# Micro_Control_Board_-_V130.net
KiCad netlist of a schematic drawn in EAGLE
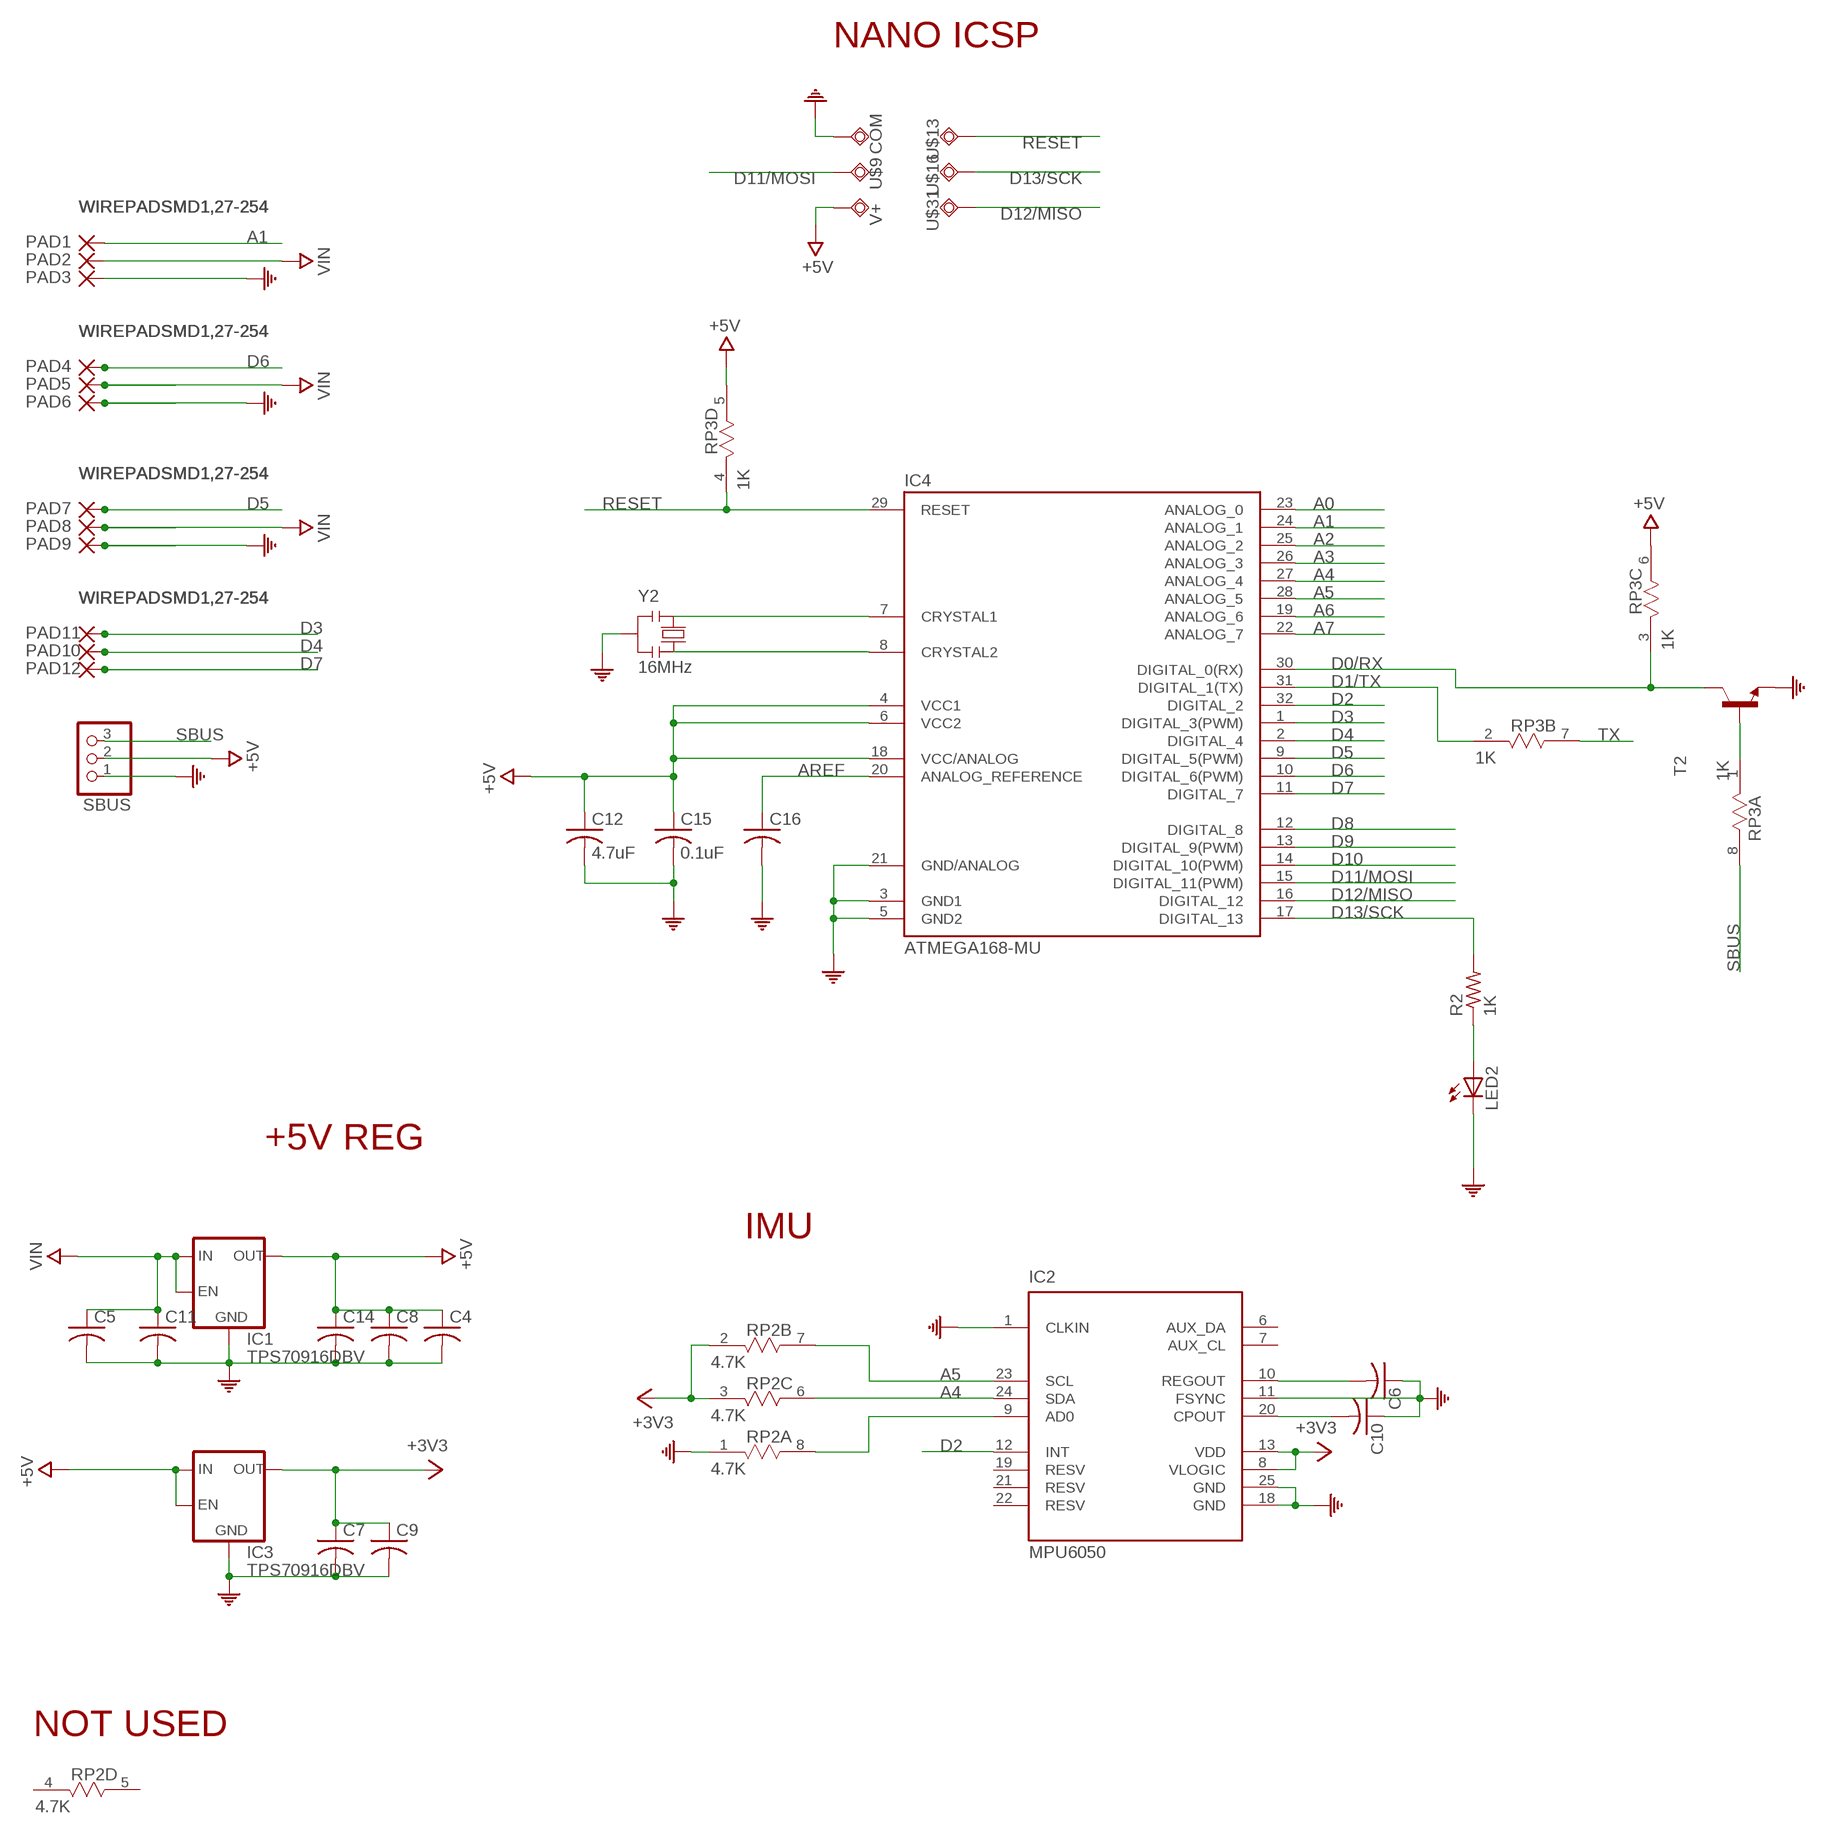
[diagram p0: schematic, sheet 1]

(export (version "E")
  (design (tool "Eeschema 10.0.6"))
  (components
    (comp (ref "C4")
      (value "C-USC0402")
      (footprint "eagle-import:C0402")
      (libsource (lib "eagle-import") (part "C-USC0402"))
    )
    (comp (ref "C5")
      (value "C-USC0402")
      (footprint "eagle-import:C0402")
      (libsource (lib "eagle-import") (part "C-USC0402"))
    )
    (comp (ref "C6")
      (value "C-USC0402")
      (footprint "eagle-import:C0402")
      (libsource (lib "eagle-import") (part "C-USC0402"))
    )
    (comp (ref "C7")
      (value "C-USC0402")
      (footprint "eagle-import:C0402")
      (libsource (lib "eagle-import") (part "C-USC0402"))
    )
    (comp (ref "C8")
      (value "C-USC0402")
      (footprint "eagle-import:C0402")
      (libsource (lib "eagle-import") (part "C-USC0402"))
    )
    (comp (ref "C9")
      (value "C-USC0402")
      (footprint "eagle-import:C0402")
      (libsource (lib "eagle-import") (part "C-USC0402"))
    )
    (comp (ref "C10")
      (value "C-USC0402")
      (footprint "eagle-import:C0402")
      (libsource (lib "eagle-import") (part "C-USC0402"))
    )
    (comp (ref "C11")
      (value "C-USC0402")
      (footprint "eagle-import:C0402")
      (libsource (lib "eagle-import") (part "C-USC0402"))
    )
    (comp (ref "C12")
      (value "4.7uF")
      (footprint "eagle-import:C0402")
      (libsource (lib "eagle-import") (part "C-USC0402"))
    )
    (comp (ref "C14")
      (value "C-USC0402")
      (footprint "eagle-import:C0402")
      (libsource (lib "eagle-import") (part "C-USC0402"))
    )
    (comp (ref "C15")
      (value "0.1uF")
      (footprint "eagle-import:C0402")
      (libsource (lib "eagle-import") (part "C-USC0402"))
    )
    (comp (ref "C16")
      (value "C-USC0402")
      (footprint "eagle-import:C0402")
      (libsource (lib "eagle-import") (part "C-USC0402"))
    )
    (comp (ref "COM")
      (value "0.7MM-THRU")
      (footprint "eagle-import:0.65MM-THRU")
      (libsource (lib "eagle-import") (part "0.7MM-THRU"))
    )
    (comp (ref "IC1")
      (value "TPS70916DBV")
      (footprint "eagle-import:SOT23-5")
      (fields (field (name "MF") "Texas Instruments") (field (name "MPN") "TPS70916DBVT"))
      (libsource (lib "eagle-import") (part "TPS709DBV16"))
    )
    (comp (ref "IC2")
      (value "MPU6050")
      (footprint "eagle-import:QFN50P400X400X95-25T265X275N")
      (libsource (lib "eagle-import") (part "MPU6050"))
    )
    (comp (ref "IC3")
      (value "TPS70916DBV")
      (footprint "eagle-import:SOT23-5")
      (fields (field (name "MF") "Texas Instruments") (field (name "MPN") "TPS70916DBVT"))
      (libsource (lib "eagle-import") (part "TPS709DBV16"))
    )
    (comp (ref "IC4")
      (value "ATMEGA168-MU")
      (footprint "eagle-import:MLF32")
      (libsource (lib "eagle-import") (part "ATMEGA168-MU"))
    )
    (comp (ref "LED2")
      (value "LEDCHIP-LED0603")
      (footprint "eagle-import:CHIP-LED0603")
      (libsource (lib "eagle-import") (part "LEDCHIP-LED0603"))
    )
    (comp (ref "PAD1")
      (value "WIREPADSMD1,27-254")
      (footprint "eagle-import:SMD1,27-2,54")
      (libsource (lib "eagle-import") (part "WIREPADSMD1,27-254"))
    )
    (comp (ref "PAD2")
      (value "WIREPADSMD1,27-254")
      (footprint "eagle-import:SMD1,27-2,54")
      (libsource (lib "eagle-import") (part "WIREPADSMD1,27-254"))
    )
    (comp (ref "PAD3")
      (value "WIREPADSMD1,27-254")
      (footprint "eagle-import:SMD1,27-2,54")
      (libsource (lib "eagle-import") (part "WIREPADSMD1,27-254"))
    )
    (comp (ref "PAD4")
      (value "WIREPADSMD1,27-254")
      (footprint "eagle-import:SMD1,27-2,54")
      (libsource (lib "eagle-import") (part "WIREPADSMD1,27-254"))
    )
    (comp (ref "PAD5")
      (value "WIREPADSMD1,27-254")
      (footprint "eagle-import:SMD1,27-2,54")
      (libsource (lib "eagle-import") (part "WIREPADSMD1,27-254"))
    )
    (comp (ref "PAD6")
      (value "WIREPADSMD1,27-254")
      (footprint "eagle-import:SMD1,27-2,54")
      (libsource (lib "eagle-import") (part "WIREPADSMD1,27-254"))
    )
    (comp (ref "PAD7")
      (value "WIREPADSMD1,27-254")
      (footprint "eagle-import:SMD1,27-2,54")
      (libsource (lib "eagle-import") (part "WIREPADSMD1,27-254"))
    )
    (comp (ref "PAD8")
      (value "WIREPADSMD1,27-254")
      (footprint "eagle-import:SMD1,27-2,54")
      (libsource (lib "eagle-import") (part "WIREPADSMD1,27-254"))
    )
    (comp (ref "PAD9")
      (value "WIREPADSMD1,27-254")
      (footprint "eagle-import:SMD1,27-2,54")
      (libsource (lib "eagle-import") (part "WIREPADSMD1,27-254"))
    )
    (comp (ref "PAD10")
      (value "WIREPADSMD1,27-254")
      (footprint "eagle-import:SMD1,27-2,54")
      (libsource (lib "eagle-import") (part "WIREPADSMD1,27-254"))
    )
    (comp (ref "PAD11")
      (value "WIREPADSMD1,27-254")
      (footprint "eagle-import:SMD1,27-2,54")
      (libsource (lib "eagle-import") (part "WIREPADSMD1,27-254"))
    )
    (comp (ref "PAD12")
      (value "WIREPADSMD1,27-254")
      (footprint "eagle-import:SMD1,27-2,54")
      (libsource (lib "eagle-import") (part "WIREPADSMD1,27-254"))
    )
    (comp (ref "R2")
      (value "1K")
      (footprint "eagle-import:R0402")
      (libsource (lib "eagle-import") (part "R-US_R0402"))
    )
    (comp (ref "RP2")
      (value "4.7K")
      (footprint "eagle-import:RES4NT")
      (libsource (lib "eagle-import") (part "RES4NT"))
    )
    (comp (ref "RP3")
      (value "1K")
      (footprint "eagle-import:RES4NT")
      (libsource (lib "eagle-import") (part "RES4NT"))
    )
    (comp (ref "SBUS")
      (value "PINHD-1X3")
      (footprint "eagle-import:1X03")
      (libsource (lib "eagle-import") (part "PINHD-1X3"))
    )
    (comp (ref "T2")
      (value "MMBT3904LT1-NPN-SOT23-BEC")
      (footprint "eagle-import:SOT23-BEC")
      (libsource (lib "eagle-import") (part "-NPN-SOT23-BECMMBT3904LT1"))
    )
    (comp (ref "U$9")
      (value "0.7MM-THRU")
      (footprint "eagle-import:0.65MM-THRU")
      (libsource (lib "eagle-import") (part "0.7MM-THRU"))
    )
    (comp (ref "U$13")
      (value "0.7MM-THRU")
      (footprint "eagle-import:0.65MM-THRU")
      (libsource (lib "eagle-import") (part "0.7MM-THRU"))
    )
    (comp (ref "U$16")
      (value "0.7MM-THRU")
      (footprint "eagle-import:0.65MM-THRU")
      (libsource (lib "eagle-import") (part "0.7MM-THRU"))
    )
    (comp (ref "U$31")
      (value "0.7MM-THRU")
      (footprint "eagle-import:0.65MM-THRU")
      (libsource (lib "eagle-import") (part "0.7MM-THRU"))
    )
    (comp (ref "V+")
      (value "0.7MM-THRU")
      (footprint "eagle-import:0.65MM-THRU")
      (libsource (lib "eagle-import") (part "0.7MM-THRU"))
    )
    (comp (ref "Y2")
      (value "16MHz")
      (footprint "eagle-import:RESONATOR")
      (libsource (lib "eagle-import") (part "RESONATORMU"))
    )
  )
  (nets
    (net (code "1") (name "+3V3") (class "Default")
      (node (ref "C7") (pin "1") (pinfunction "1_1") (pintype "passive"))
      (node (ref "C9") (pin "1") (pinfunction "1_1") (pintype "passive"))
      (node (ref "IC2") (pin "13") (pinfunction "VDD_13") (pintype "power_in"))
      (node (ref "IC2") (pin "8") (pinfunction "VLOGIC_8") (pintype "power_in"))
      (node (ref "IC3") (pin "5") (pinfunction "OUT_5") (pintype "passive"))
      (node (ref "RP2") (pin "2") (pinfunction "1_2") (pintype "passive"))
      (node (ref "RP2") (pin "3") (pinfunction "1_3") (pintype "passive"))
    )
    (net (code "2") (name "+5V") (class "Default")
      (node (ref "C12") (pin "1") (pinfunction "1_1") (pintype "passive"))
      (node (ref "C14") (pin "1") (pinfunction "1_1") (pintype "passive"))
      (node (ref "C15") (pin "1") (pinfunction "1_1") (pintype "passive"))
      (node (ref "C4") (pin "1") (pinfunction "1_1") (pintype "passive"))
      (node (ref "C8") (pin "1") (pinfunction "1_1") (pintype "passive"))
      (node (ref "IC1") (pin "5") (pinfunction "OUT_5") (pintype "passive"))
      (node (ref "IC3") (pin "1") (pinfunction "IN_1") (pintype "input"))
      (node (ref "IC3") (pin "3") (pinfunction "EN_3") (pintype "input"))
      (node (ref "IC4") (pin "18") (pinfunction "VCC/ANALOG_18") (pintype "passive"))
      (node (ref "IC4") (pin "4") (pinfunction "VCC1_4") (pintype "power_in"))
      (node (ref "IC4") (pin "6") (pinfunction "VCC2_6") (pintype "power_in"))
      (node (ref "RP3") (pin "5") (pinfunction "2_5") (pintype "passive"))
      (node (ref "RP3") (pin "6") (pinfunction "2_6") (pintype "passive"))
      (node (ref "SBUS") (pin "2") (pinfunction "2_2") (pintype "passive"))
      (node (ref "V+") (pin "P$2") (pinfunction "TP_P$2") (pintype "input"))
    )
    (net (code "3") (name "/A0") (class "Default")
      (node (ref "IC4") (pin "23") (pinfunction "ANALOG_0_23") (pintype "bidirectional"))
    )
    (net (code "4") (name "/A1") (class "Default")
      (node (ref "IC4") (pin "24") (pinfunction "ANALOG_1_24") (pintype "bidirectional"))
      (node (ref "PAD1") (pin "1") (pinfunction "P_1") (pintype "passive"))
    )
    (net (code "5") (name "/A2") (class "Default")
      (node (ref "IC4") (pin "25") (pinfunction "ANALOG_2_25") (pintype "bidirectional"))
    )
    (net (code "6") (name "/A3") (class "Default")
      (node (ref "IC4") (pin "26") (pinfunction "ANALOG_3_26") (pintype "bidirectional"))
    )
    (net (code "7") (name "/A4") (class "Default")
      (node (ref "IC2") (pin "24") (pinfunction "SDA_24") (pintype "bidirectional"))
      (node (ref "IC4") (pin "27") (pinfunction "ANALOG_4_27") (pintype "bidirectional"))
      (node (ref "RP2") (pin "6") (pinfunction "2_6") (pintype "passive"))
    )
    (net (code "8") (name "/A5") (class "Default")
      (node (ref "IC2") (pin "23") (pinfunction "SCL_23") (pintype "input"))
      (node (ref "IC4") (pin "28") (pinfunction "ANALOG_5_28") (pintype "bidirectional"))
      (node (ref "RP2") (pin "7") (pinfunction "2_7") (pintype "passive"))
    )
    (net (code "9") (name "/A6") (class "Default")
      (node (ref "IC4") (pin "19") (pinfunction "ANALOG_6_19") (pintype "passive"))
    )
    (net (code "10") (name "/A7") (class "Default")
      (node (ref "IC4") (pin "22") (pinfunction "ANALOG_7_22") (pintype "passive"))
    )
    (net (code "11") (name "/AREF") (class "Default")
      (node (ref "C16") (pin "1") (pinfunction "1_1") (pintype "passive"))
      (node (ref "IC4") (pin "20") (pinfunction "ANALOG_REFERENCE_20") (pintype "passive"))
    )
    (net (code "12") (name "/D0{slash}RX") (class "Default")
      (node (ref "IC4") (pin "30") (pinfunction "DIGITAL_0(RX)_30") (pintype "bidirectional"))
      (node (ref "RP3") (pin "3") (pinfunction "1_3") (pintype "passive"))
      (node (ref "T2") (pin "C") (pinfunction "C_C") (pintype "passive"))
    )
    (net (code "13") (name "/D1{slash}TX") (class "Default")
      (node (ref "IC4") (pin "31") (pinfunction "DIGITAL_1(TX)_31") (pintype "bidirectional"))
      (node (ref "RP3") (pin "2") (pinfunction "1_2") (pintype "passive"))
    )
    (net (code "14") (name "/D2") (class "Default")
      (node (ref "IC2") (pin "12") (pinfunction "INT_12") (pintype "open_collector"))
      (node (ref "IC4") (pin "32") (pinfunction "DIGITAL_2_32") (pintype "bidirectional"))
    )
    (net (code "15") (name "/D3") (class "Default")
      (node (ref "IC4") (pin "1") (pinfunction "DIGITAL_3(PWM)_1") (pintype "bidirectional"))
      (node (ref "PAD10") (pin "1") (pinfunction "P_1") (pintype "passive"))
    )
    (net (code "16") (name "/D4") (class "Default")
      (node (ref "IC4") (pin "2") (pinfunction "DIGITAL_4_2") (pintype "bidirectional"))
      (node (ref "PAD11") (pin "1") (pinfunction "P_1") (pintype "passive"))
    )
    (net (code "17") (name "/D5") (class "Default")
      (node (ref "IC4") (pin "9") (pinfunction "DIGITAL_5(PWM)_9") (pintype "bidirectional"))
      (node (ref "PAD7") (pin "1") (pinfunction "P_1") (pintype "passive"))
    )
    (net (code "18") (name "/D6") (class "Default")
      (node (ref "IC4") (pin "10") (pinfunction "DIGITAL_6(PWM)_10") (pintype "bidirectional"))
      (node (ref "PAD4") (pin "1") (pinfunction "P_1") (pintype "passive"))
    )
    (net (code "19") (name "/D7") (class "Default")
      (node (ref "IC4") (pin "11") (pinfunction "DIGITAL_7_11") (pintype "bidirectional"))
      (node (ref "PAD12") (pin "1") (pinfunction "P_1") (pintype "passive"))
    )
    (net (code "20") (name "/D8") (class "Default")
      (node (ref "IC4") (pin "12") (pinfunction "DIGITAL_8_12") (pintype "bidirectional"))
    )
    (net (code "21") (name "/D9") (class "Default")
      (node (ref "IC4") (pin "13") (pinfunction "DIGITAL_9(PWM)_13") (pintype "bidirectional"))
    )
    (net (code "22") (name "/D10") (class "Default")
      (node (ref "IC4") (pin "14") (pinfunction "DIGITAL_10(PWM)_14") (pintype "bidirectional"))
    )
    (net (code "23") (name "/D11{slash}MOSI") (class "Default")
      (node (ref "IC4") (pin "15") (pinfunction "DIGITAL_11(PWM)_15") (pintype "bidirectional"))
      (node (ref "U$9") (pin "P$2") (pinfunction "TP_P$2") (pintype "input"))
    )
    (net (code "24") (name "/D12{slash}MISO") (class "Default")
      (node (ref "IC4") (pin "16") (pinfunction "DIGITAL_12_16") (pintype "bidirectional"))
      (node (ref "U$31") (pin "P$2") (pinfunction "TP_P$2") (pintype "input"))
    )
    (net (code "25") (name "/D13{slash}SCK") (class "Default")
      (node (ref "IC4") (pin "17") (pinfunction "DIGITAL_13_17") (pintype "bidirectional"))
      (node (ref "R2") (pin "2") (pinfunction "2_2") (pintype "passive"))
      (node (ref "U$16") (pin "P$2") (pinfunction "TP_P$2") (pintype "input"))
    )
    (net (code "26") (name "/RESET") (class "Default")
      (node (ref "IC4") (pin "29") (pinfunction "RESET_29") (pintype "bidirectional"))
      (node (ref "RP3") (pin "4") (pinfunction "1_4") (pintype "passive"))
      (node (ref "U$13") (pin "P$2") (pinfunction "TP_P$2") (pintype "input"))
    )
    (net (code "27") (name "/SBUS") (class "Default")
      (node (ref "RP3") (pin "8") (pinfunction "2_8") (pintype "passive"))
      (node (ref "SBUS") (pin "3") (pinfunction "3_3") (pintype "passive"))
    )
    (net (code "28") (name "/TX") (class "Default")
      (node (ref "RP3") (pin "7") (pinfunction "2_7") (pintype "passive"))
    )
    (net (code "29") (name "COM") (class "Default")
      (node (ref "C10") (pin "1") (pinfunction "1_1") (pintype "passive"))
      (node (ref "C11") (pin "2") (pinfunction "2_2") (pintype "passive"))
      (node (ref "C12") (pin "2") (pinfunction "2_2") (pintype "passive"))
      (node (ref "C14") (pin "2") (pinfunction "2_2") (pintype "passive"))
      (node (ref "C15") (pin "2") (pinfunction "2_2") (pintype "passive"))
      (node (ref "C16") (pin "2") (pinfunction "2_2") (pintype "passive"))
      (node (ref "C4") (pin "2") (pinfunction "2_2") (pintype "passive"))
      (node (ref "C5") (pin "2") (pinfunction "2_2") (pintype "passive"))
      (node (ref "C6") (pin "1") (pinfunction "1_1") (pintype "passive"))
      (node (ref "C7") (pin "2") (pinfunction "2_2") (pintype "passive"))
      (node (ref "C8") (pin "2") (pinfunction "2_2") (pintype "passive"))
      (node (ref "C9") (pin "2") (pinfunction "2_2") (pintype "passive"))
      (node (ref "COM") (pin "P$2") (pinfunction "TP_P$2") (pintype "input"))
      (node (ref "IC1") (pin "2") (pinfunction "GND_2") (pintype "input"))
      (node (ref "IC2") (pin "1") (pinfunction "CLKIN_1") (pintype "input"))
      (node (ref "IC2") (pin "11") (pinfunction "FSYNC_11") (pintype "input"))
      (node (ref "IC2") (pin "18") (pinfunction "GND_18") (pintype "power_in"))
      (node (ref "IC2") (pin "25") (pinfunction "GND_25") (pintype "power_in"))
      (node (ref "IC3") (pin "2") (pinfunction "GND_2") (pintype "input"))
      (node (ref "IC4") (pin "21") (pinfunction "GND/ANALOG_21") (pintype "power_in"))
      (node (ref "IC4") (pin "3") (pinfunction "GND1_3") (pintype "power_in"))
      (node (ref "IC4") (pin "5") (pinfunction "GND2_5") (pintype "power_in"))
      (node (ref "LED2") (pin "C") (pinfunction "C_C") (pintype "passive"))
      (node (ref "PAD3") (pin "1") (pinfunction "P_1") (pintype "passive"))
      (node (ref "PAD6") (pin "1") (pinfunction "P_1") (pintype "passive"))
      (node (ref "PAD9") (pin "1") (pinfunction "P_1") (pintype "passive"))
      (node (ref "RP2") (pin "1") (pinfunction "1_1") (pintype "passive"))
      (node (ref "SBUS") (pin "1") (pinfunction "1_1") (pintype "passive"))
      (node (ref "T2") (pin "E") (pinfunction "E_E") (pintype "passive"))
      (node (ref "Y2") (pin "2") (pinfunction "2_2") (pintype "passive"))
    )
    (net (code "30") (name "Net-(IC2A-AD0)") (class "Default")
      (node (ref "IC2") (pin "9") (pinfunction "AD0_9") (pintype "input"))
      (node (ref "RP2") (pin "8") (pinfunction "2_8") (pintype "passive"))
    )
    (net (code "31") (name "Net-(IC2A-CPOUT)") (class "Default")
      (node (ref "C10") (pin "2") (pinfunction "2_2") (pintype "passive"))
      (node (ref "IC2") (pin "20") (pinfunction "CPOUT_20") (pintype "output"))
    )
    (net (code "32") (name "Net-(IC2A-REGOUT)") (class "Default")
      (node (ref "C6") (pin "2") (pinfunction "2_2") (pintype "passive"))
      (node (ref "IC2") (pin "10") (pinfunction "REGOUT_10") (pintype "output"))
    )
    (net (code "33") (name "Net-(IC4-CRYSTAL1)") (class "Default")
      (node (ref "IC4") (pin "7") (pinfunction "CRYSTAL1_7") (pintype "bidirectional"))
      (node (ref "Y2") (pin "1") (pinfunction "1_1") (pintype "passive"))
    )
    (net (code "34") (name "Net-(IC4-CRYSTAL2)") (class "Default")
      (node (ref "IC4") (pin "8") (pinfunction "CRYSTAL2_8") (pintype "bidirectional"))
      (node (ref "Y2") (pin "3") (pinfunction "3_3") (pintype "passive"))
    )
    (net (code "35") (name "Net-(LED2-PadA)") (class "Default")
      (node (ref "LED2") (pin "A") (pinfunction "A_A") (pintype "passive"))
      (node (ref "R2") (pin "1") (pinfunction "1_1") (pintype "passive"))
    )
    (net (code "36") (name "Net-(RP3-Pad1)") (class "Default")
      (node (ref "RP3") (pin "1") (pinfunction "1_1") (pintype "passive"))
      (node (ref "T2") (pin "B") (pinfunction "B_B") (pintype "passive"))
    )
    (net (code "37") (name "VIN") (class "Default")
      (node (ref "C11") (pin "1") (pinfunction "1_1") (pintype "passive"))
      (node (ref "C5") (pin "1") (pinfunction "1_1") (pintype "passive"))
      (node (ref "IC1") (pin "1") (pinfunction "IN_1") (pintype "input"))
      (node (ref "IC1") (pin "3") (pinfunction "EN_3") (pintype "input"))
      (node (ref "PAD2") (pin "1") (pinfunction "P_1") (pintype "passive"))
      (node (ref "PAD5") (pin "1") (pinfunction "P_1") (pintype "passive"))
      (node (ref "PAD8") (pin "1") (pinfunction "P_1") (pintype "passive"))
    )
    (net (code "38") (name "unconnected-(IC2A-AUX_CL-Pad7)") (class "Default")
      (node (ref "IC2") (pin "7") (pinfunction "AUX_CL_7") (pintype "bidirectional"))
    )
    (net (code "39") (name "unconnected-(IC2A-AUX_DA-Pad6)") (class "Default")
      (node (ref "IC2") (pin "6") (pinfunction "AUX_DA_6") (pintype "bidirectional"))
    )
    (net (code "40") (name "unconnected-(IC2A-RESV-Pad19)") (class "Default")
      (node (ref "IC2") (pin "19") (pinfunction "RESV_19") (pintype "passive"))
    )
    (net (code "41") (name "unconnected-(IC2A-RESV-Pad21)") (class "Default")
      (node (ref "IC2") (pin "21") (pinfunction "RESV_21") (pintype "passive"))
    )
    (net (code "42") (name "unconnected-(IC2A-RESV-Pad22)") (class "Default")
      (node (ref "IC2") (pin "22") (pinfunction "RESV_22") (pintype "passive"))
    )
    (net (code "43") (name "unconnected-(RP2D-1-Pad4)") (class "Default")
      (node (ref "RP2") (pin "4") (pinfunction "1_4") (pintype "passive"))
    )
    (net (code "44") (name "unconnected-(RP2D-2-Pad5)") (class "Default")
      (node (ref "RP2") (pin "5") (pinfunction "2_5") (pintype "passive"))
    )
  )
)
